# Power_Battery_Measurement.net
KiCad netlist of a schematic drawn in Altium Designer
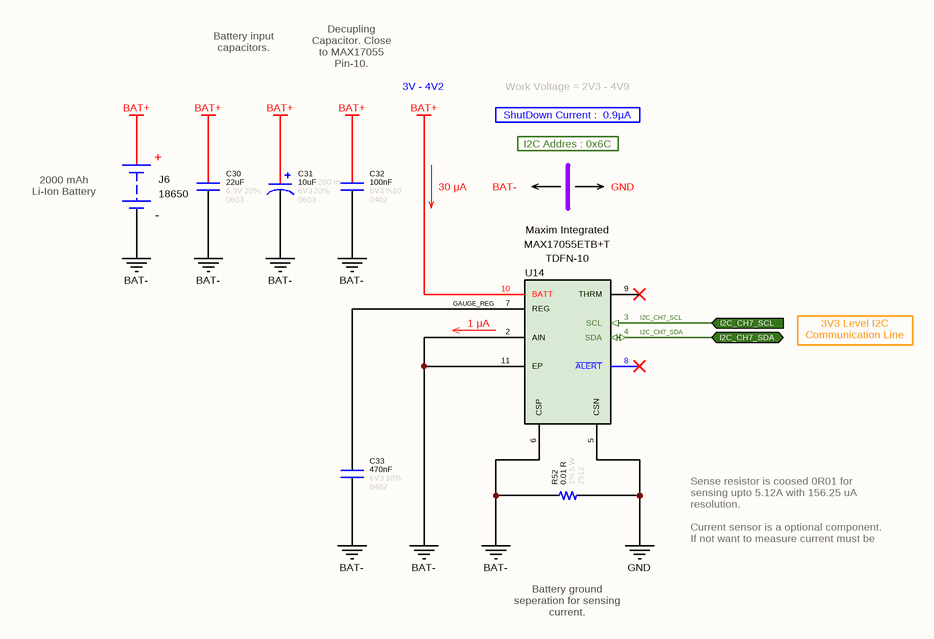
[diagram p0: Power Battery Measurement.SchDoc]

(export (version "E")
  (design (tool "Eeschema 10.0.6"))
  (components
    (comp (ref "C30")
      (value "22uF")
      (footprint "CAPACITOR_0603")
      (description "Multilayer Ceramic Capacitors - SMD - 6V3 22uF X5R 0603 20%")
      (fields
        (field (name "MANUFACTURER PART NUMBER") "GRM188R60J226MEA0D")
        (field (name "TOLERANCE") "20%")
        (field (name "CASE") "0603")
        (field (name "VOLTAGE") "6.3V")
        (field (name "Comment") "Capacitor - 22uF [0603] (Ceramic)")
      )
      (libsource (lib "Akkoyun") (part "Capacitor - 22uF [0603-6V3]"))
    )
    (comp (ref "C31")
      (value "10uF")
      (footprint "CAPACITOR_0603_Tantalum")
      (description "Capacitor - 10uF [0603] (Tantalium)")
      (fields
        (field (name "MANUFACTURER PART NUMBER") "F380J106MMAAH3")
        (field (name "ESR") "200 m")
        (field (name "TOLERANCE") "20%")
        (field (name "CASE") "0603")
        (field (name "VOLTAGE") "6V3")
        (field (name "Comment") "Capacitor - 10uF [0603] (Tantalum)")
      )
      (libsource (lib "Akkoyun") (part "Capacitor - 10uF [0603-6V3] (Tantalium)"))
    )
    (comp (ref "C32")
      (value "100nF")
      (footprint "CAPACITOR_0402")
      (description "Capacitor - 100nF [0402-6V3] (Ceramic)")
      (fields
        (field (name "MANUFACTURER PART NUMBER") "04026D104KAT4A")
        (field (name "TOLERANCE") "%10")
        (field (name "VOLTAGE") "6V3")
        (field (name "CASE") "0402")
        (field (name "Comment") "Capacitor - 100nF [0402] (Ceramic)")
      )
      (libsource (lib "Akkoyun") (part "Capacitor - 100nF [0402-6V3]"))
    )
    (comp (ref "C33")
      (value "470nF")
      (footprint "CAPACITOR_0402")
      (description "Multilayer Ceramic Capacitors - SMD - 6.3V 470nF X7R 0402 10%")
      (fields
        (field (name "MANUFACTURER PART NUMBER") "04026C474KAT2A")
        (field (name "TOLERANCE") "10%")
        (field (name "CASE") "0402")
        (field (name "VOLTAGE") "6V3")
        (field (name "Comment") "Capacitor - 470nF [0402] (Ceramic)")
      )
      (libsource (lib "Akkoyun") (part "Capacitor - 470 nF [0402-6V3]"))
    )
    (comp (ref "J6")
      (value "54")
      (footprint "BATTERY_HOLDER - Bat - V2")
      (description "BATTERY CONTACT CLP 18650 PC PIN")
      (fields (field (name "BATTERY SIZE") "18650"))
      (libsource (lib "Akkoyun") (part "Connector - 18650 Battery Holder 2"))
    )
    (comp (ref "R52")
      (value "0.01 R")
      (footprint "RESISTOR_2512 SHUNT")
      (description "Shunt Resistors - SMD 5 W 0.01 Ohm 1%")
      (fields
        (field (name "MANUFACTURER PART NUMBER") "TLRH3APTTE10L0F")
        (field (name "TOLERANCE") "1%")
        (field (name "POWER") "5 W")
        (field (name "CASE") "2512")
        (field (name "Comment") "0R01 - 2512 - %1 - 5W")
      )
      (libsource (lib "Akkoyun") (part "Resistor - 0R01 [2512]"))
    )
    (comp (ref "U14")
      (value "MAX17055ETB+T")
      (footprint "TDFN-10")
      (description "IC FUEL GAUGE MODELGAUGE 10TDFN")
      (fields
        (field (name "MANUFACTURER NAME") "Maxim Integrated")
        (field (name "MANUFACTURER PART NUMBER") "MAX17055ETB+T")
        (field (name "CASE") "TDFN-10")
      )
      (libsource (lib "Akkoyun") (part "IC - MAX17055"))
    )
  )
  (nets
    (net (code "1") (name "/GAUGE_REG") (class "Default")
      (node (ref "C33") (pin "2") (pinfunction "2_2") (pintype "passive"))
      (node (ref "U14") (pin "7") (pinfunction "REG_7") (pintype "passive"))
    )
    (net (code "2") (name "/I2C_CH7_SCL") (class "Default")
      (node (ref "U14") (pin "3") (pinfunction "SCL_3") (pintype "input"))
    )
    (net (code "3") (name "/I2C_CH7_SDA") (class "Default")
      (node (ref "U14") (pin "4") (pinfunction "SDA_4") (pintype "bidirectional"))
    )
    (net (code "4") (name "BAT+") (class "Default")
      (node (ref "C30") (pin "2") (pinfunction "2_2") (pintype "passive"))
      (node (ref "C31") (pin "1") (pinfunction "1_1") (pintype "passive"))
      (node (ref "C32") (pin "2") (pinfunction "2_2") (pintype "passive"))
      (node (ref "J6") (pin "1") (pinfunction "BAT+_1") (pintype "power_in"))
      (node (ref "U14") (pin "10") (pinfunction "BATT_10") (pintype "power_in"))
    )
    (net (code "5") (name "BAT-") (class "Default")
      (node (ref "C30") (pin "1") (pinfunction "1_1") (pintype "passive"))
      (node (ref "C31") (pin "2") (pinfunction "2_2") (pintype "passive"))
      (node (ref "C32") (pin "1") (pinfunction "1_1") (pintype "passive"))
      (node (ref "C33") (pin "1") (pinfunction "1_1") (pintype "passive"))
      (node (ref "J6") (pin "2") (pinfunction "BAT-_2") (pintype "power_in"))
      (node (ref "R52") (pin "2") (pinfunction "2_2") (pintype "passive"))
      (node (ref "U14") (pin "11") (pinfunction "EP_11") (pintype "passive"))
      (node (ref "U14") (pin "2") (pinfunction "AIN_2") (pintype "passive"))
      (node (ref "U14") (pin "6") (pinfunction "CSP_6") (pintype "power_in"))
    )
    (net (code "6") (name "GND") (class "Default")
      (node (ref "R52") (pin "1") (pinfunction "1_1") (pintype "passive"))
      (node (ref "U14") (pin "5") (pinfunction "CSN_5") (pintype "power_in"))
    )
    (net (code "7") (name "unconnected-(U14-THRM-Pad9)") (class "Default")
      (node (ref "U14") (pin "9") (pinfunction "THRM_9") (pintype "passive+no_connect"))
    )
    (net (code "8") (name "unconnected-(U14-~{ALERT}-Pad8)") (class "Default")
      (node (ref "U14") (pin "8") (pinfunction "~{ALERT}_8") (pintype "open_collector+no_connect"))
    )
  )
)
